# 3v3.net
KiCad netlist of a schematic drawn in EAGLE
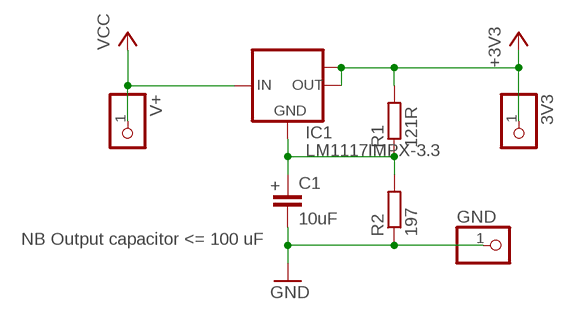
[diagram p0: schematic, sheet 1]

(export (version "E")
  (design (tool "Eeschema 10.0.6"))
  (components
    (comp (ref "3V3")
      (value "PINHD-1X1")
      (footprint "eagle-import:1X01")
      (libsource (lib "eagle-import") (part "PINHD-1X1"))
    )
    (comp (ref "C1")
      (value "10uF")
      (footprint "eagle-import:C0805")
      (libsource (lib "eagle-import") (part "C-EUC0805"))
    )
    (comp (ref "GND")
      (value "PINHD-1X1")
      (footprint "eagle-import:1X01")
      (libsource (lib "eagle-import") (part "PINHD-1X1"))
    )
    (comp (ref "IC1")
      (value "LM1117IMPX-3.3")
      (footprint "eagle-import:SOT223")
      (libsource (lib "eagle-import") (part "LM1117IMPX-3.3"))
    )
    (comp (ref "R1")
      (value "121R")
      (footprint "eagle-import:M0805")
      (libsource (lib "eagle-import") (part "R-EU_M0805"))
    )
    (comp (ref "R2")
      (value "197")
      (footprint "eagle-import:M0805")
      (libsource (lib "eagle-import") (part "R-EU_M0805"))
    )
    (comp (ref "V+")
      (value "PINHD-1X1")
      (footprint "eagle-import:1X01")
      (libsource (lib "eagle-import") (part "PINHD-1X1"))
    )
  )
  (nets
    (net (code "1") (name "+3V3") (class "Default")
      (node (ref "3V3") (pin "1") (pinfunction "1_1") (pintype "passive"))
      (node (ref "IC1") (pin "2") (pinfunction "OUT_2") (pintype "passive"))
      (node (ref "IC1") (pin "TAB") (pinfunction "OUT1_TAB") (pintype "passive"))
      (node (ref "R1") (pin "2") (pinfunction "2_2") (pintype "passive"))
    )
    (net (code "2") (name "GND") (class "Default")
      (node (ref "C1") (pin "2") (pinfunction "2_2") (pintype "passive"))
      (node (ref "GND") (pin "1") (pinfunction "1_1") (pintype "passive"))
      (node (ref "R2") (pin "1") (pinfunction "1_1") (pintype "passive"))
    )
    (net (code "3") (name "Net-(IC1-GND)") (class "Default")
      (node (ref "C1") (pin "1") (pinfunction "1_1") (pintype "passive"))
      (node (ref "IC1") (pin "1") (pinfunction "GND_1") (pintype "input"))
      (node (ref "R1") (pin "1") (pinfunction "1_1") (pintype "passive"))
      (node (ref "R2") (pin "2") (pinfunction "2_2") (pintype "passive"))
    )
    (net (code "4") (name "VCC") (class "Default")
      (node (ref "IC1") (pin "3") (pinfunction "IN_3") (pintype "input"))
      (node (ref "V+") (pin "1") (pinfunction "1_1") (pintype "passive"))
    )
  )
)
